# sparkfun-mlx90640-qwiic-breakout-55.net
KiCad netlist of a schematic drawn in EAGLE
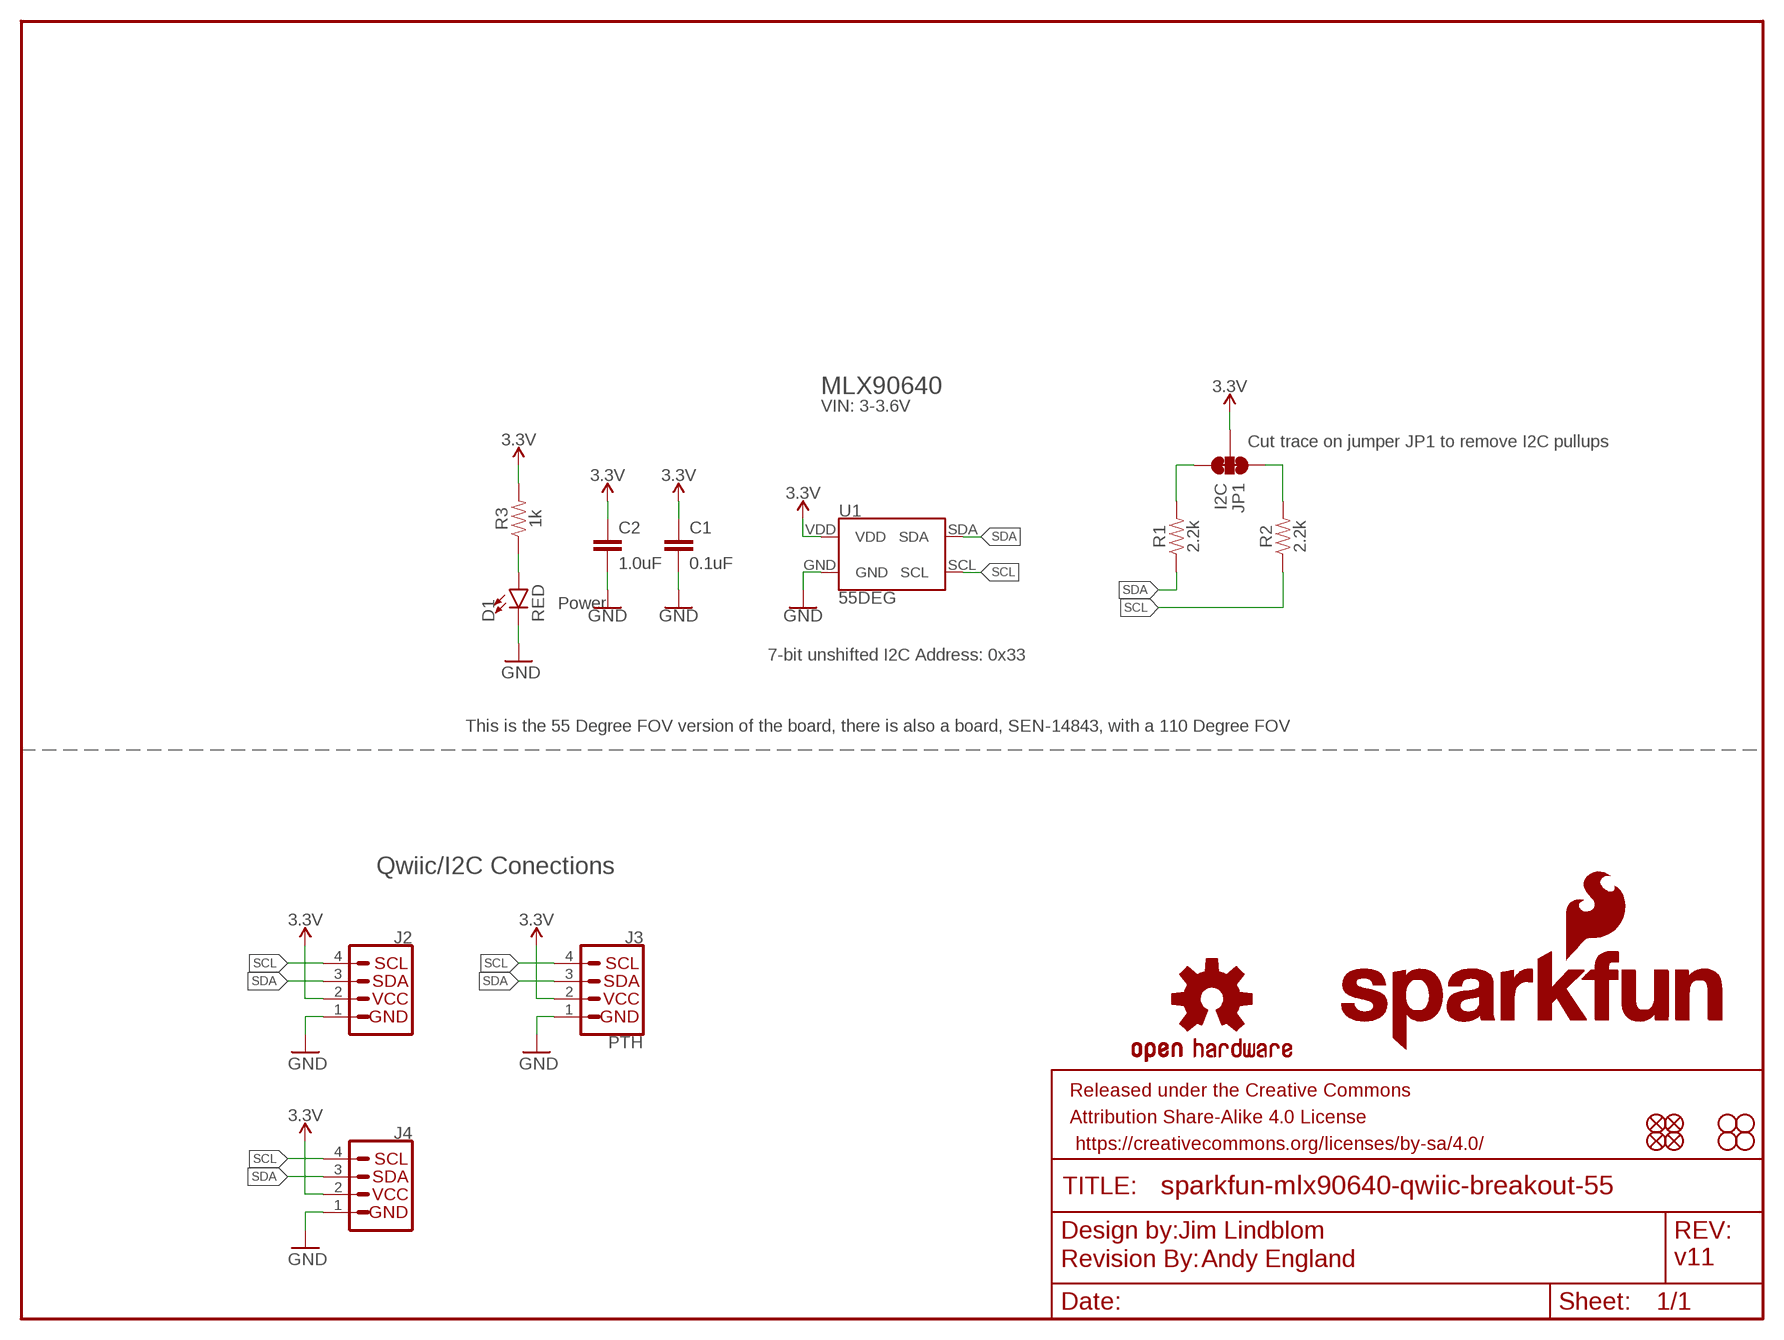
[diagram p0: schematic, sheet 1]

(export (version "E")
  (design (tool "Eeschema 10.0.6"))
  (components
    (comp (ref "C1")
      (value "0.1uF")
      (footprint "eagle-import:0603")
      (libsource (lib "eagle-import") (part "0.1UF-0603-25V-(+80/-20%)"))
    )
    (comp (ref "C2")
      (value "1.0uF")
      (footprint "eagle-import:0603")
      (libsource (lib "eagle-import") (part "1.0UF-0603-16V-10%"))
    )
    (comp (ref "D1")
      (value "RED")
      (footprint "eagle-import:LED-0603")
      (libsource (lib "eagle-import") (part "LED-RED0603"))
    )
    (comp (ref "FRAME1")
      (value "FRAME-LETTER")
      (footprint "eagle-import:CREATIVE_COMMONS")
      (libsource (lib "eagle-import") (part "FRAME-LETTER"))
    )
    (comp (ref "J2")
      (value "QWIIC_CONNECTORJS-1MM")
      (footprint "eagle-import:1X04_1MM_RA")
      (libsource (lib "eagle-import") (part "QWIIC_CONNECTORJS-1MM"))
    )
    (comp (ref "J3")
      (value "PTH")
      (footprint "eagle-import:1X04_NO_SILK")
      (libsource (lib "eagle-import") (part "I2C_STANDARD_NO_SILK"))
    )
    (comp (ref "J4")
      (value "QWIIC_CONNECTORJS-1MM")
      (footprint "eagle-import:1X04_1MM_RA")
      (libsource (lib "eagle-import") (part "QWIIC_CONNECTORJS-1MM"))
    )
    (comp (ref "JP1")
      (value "I2C")
      (footprint "eagle-import:SMT-JUMPER_3_2-NC_TRACE_NO-SILK")
      (libsource (lib "eagle-import") (part "JUMPER-SMT_3_2-NC_TRACE_NO-SILK"))
    )
    (comp (ref "JP2")
      (value "FIDUCIALUFIDUCIAL")
      (footprint "eagle-import:MICRO-FIDUCIAL")
      (libsource (lib "eagle-import") (part "FIDUCIALUFIDUCIAL"))
    )
    (comp (ref "JP3")
      (value "STAND-OFF")
      (footprint "eagle-import:STAND-OFF")
      (libsource (lib "eagle-import") (part "STAND-OFF"))
    )
    (comp (ref "JP4")
      (value "STAND-OFF")
      (footprint "eagle-import:STAND-OFF")
      (libsource (lib "eagle-import") (part "STAND-OFF"))
    )
    (comp (ref "JP5")
      (value "FIDUCIALUFIDUCIAL")
      (footprint "eagle-import:MICRO-FIDUCIAL")
      (libsource (lib "eagle-import") (part "FIDUCIALUFIDUCIAL"))
    )
    (comp (ref "JP6")
      (value "FIDUCIALUFIDUCIAL")
      (footprint "eagle-import:MICRO-FIDUCIAL")
      (libsource (lib "eagle-import") (part "FIDUCIALUFIDUCIAL"))
    )
    (comp (ref "JP7")
      (value "FIDUCIALUFIDUCIAL")
      (footprint "eagle-import:MICRO-FIDUCIAL")
      (libsource (lib "eagle-import") (part "FIDUCIALUFIDUCIAL"))
    )
    (comp (ref "JP8")
      (value "STAND-OFF")
      (footprint "eagle-import:STAND-OFF")
      (libsource (lib "eagle-import") (part "STAND-OFF"))
    )
    (comp (ref "JP9")
      (value "STAND-OFF")
      (footprint "eagle-import:STAND-OFF")
      (libsource (lib "eagle-import") (part "STAND-OFF"))
    )
    (comp (ref "LOGO1")
      (value "OSHW-LOGOMINI")
      (footprint "eagle-import:OSHW-LOGO-MINI")
      (libsource (lib "eagle-import") (part "OSHW-LOGOMINI"))
    )
    (comp (ref "LOGO2")
      (value "SFE_LOGO_NAME_FLAME.1_INCH")
      (footprint "eagle-import:SFE_LOGO_NAME_FLAME_.1")
      (libsource (lib "eagle-import") (part "SFE_LOGO_NAME_FLAME.1_INCH"))
    )
    (comp (ref "LOGO3")
      (value "SFE_LOGO_NAME.1_INCH")
      (footprint "eagle-import:SFE_LOGO_NAME_.1")
      (libsource (lib "eagle-import") (part "SFE_LOGO_NAME.1_INCH"))
    )
    (comp (ref "LOGO4")
      (value "REVISION")
      (footprint "eagle-import:REVISION")
      (libsource (lib "eagle-import") (part "REVISION"))
    )
    (comp (ref "R1")
      (value "2.2k")
      (footprint "eagle-import:0603")
      (libsource (lib "eagle-import") (part "2.2KOHM-0603-1/10W-1%"))
    )
    (comp (ref "R2")
      (value "2.2k")
      (footprint "eagle-import:0603")
      (libsource (lib "eagle-import") (part "2.2KOHM-0603-1/10W-1%"))
    )
    (comp (ref "R3")
      (value "1k")
      (footprint "eagle-import:0603")
      (libsource (lib "eagle-import") (part "1KOHM-0603-1/10W-1%"))
    )
    (comp (ref "U1")
      (value "55DEG")
      (footprint "eagle-import:MLX90540_MLX90640")
      (libsource (lib "eagle-import") (part "MLX90540_MLX90640"))
    )
  )
  (nets
    (net (code "1") (name "3.3V") (class "Default")
      (node (ref "C1") (pin "1") (pinfunction "1_1") (pintype "passive"))
      (node (ref "C2") (pin "1") (pinfunction "1_1") (pintype "passive"))
      (node (ref "J2") (pin "2") (pinfunction "2_2") (pintype "power_in"))
      (node (ref "J3") (pin "2") (pinfunction "VCC_2") (pintype "power_in"))
      (node (ref "J4") (pin "2") (pinfunction "2_2") (pintype "power_in"))
      (node (ref "JP1") (pin "2") (pinfunction "2_2") (pintype "passive"))
      (node (ref "R3") (pin "2") (pinfunction "2_2") (pintype "passive"))
      (node (ref "U1") (pin "VDD") (pinfunction "VDD_VDD") (pintype "bidirectional"))
    )
    (net (code "2") (name "GND") (class "Default")
      (node (ref "C1") (pin "2") (pinfunction "2_2") (pintype "passive"))
      (node (ref "C2") (pin "2") (pinfunction "2_2") (pintype "passive"))
      (node (ref "D1") (pin "C") (pinfunction "C_C") (pintype "passive"))
      (node (ref "J2") (pin "1") (pinfunction "1_1") (pintype "power_in"))
      (node (ref "J3") (pin "1") (pinfunction "GND_1") (pintype "power_in"))
      (node (ref "J4") (pin "1") (pinfunction "1_1") (pintype "power_in"))
      (node (ref "U1") (pin "GND") (pinfunction "GND_GND") (pintype "bidirectional"))
    )
    (net (code "3") (name "Net-(D1-PadA)") (class "Default")
      (node (ref "D1") (pin "A") (pinfunction "A_A") (pintype "passive"))
      (node (ref "R3") (pin "1") (pinfunction "1_1") (pintype "passive"))
    )
    (net (code "4") (name "Net-(JP1-Pad1)") (class "Default")
      (node (ref "JP1") (pin "1") (pinfunction "1_1") (pintype "passive"))
      (node (ref "R2") (pin "2") (pinfunction "2_2") (pintype "passive"))
    )
    (net (code "5") (name "Net-(JP1-Pad3)") (class "Default")
      (node (ref "JP1") (pin "3") (pinfunction "3_3") (pintype "passive"))
      (node (ref "R1") (pin "2") (pinfunction "2_2") (pintype "passive"))
    )
    (net (code "6") (name "SCL") (class "Default")
      (node (ref "J2") (pin "4") (pinfunction "4_4") (pintype "passive"))
      (node (ref "J3") (pin "4") (pinfunction "SCL_4") (pintype "passive"))
      (node (ref "J4") (pin "4") (pinfunction "4_4") (pintype "passive"))
      (node (ref "R2") (pin "1") (pinfunction "1_1") (pintype "passive"))
      (node (ref "U1") (pin "SCL") (pinfunction "SCL_SCL") (pintype "bidirectional"))
    )
    (net (code "7") (name "SDA") (class "Default")
      (node (ref "J2") (pin "3") (pinfunction "3_3") (pintype "passive"))
      (node (ref "J3") (pin "3") (pinfunction "SDA_3") (pintype "passive"))
      (node (ref "J4") (pin "3") (pinfunction "3_3") (pintype "passive"))
      (node (ref "R1") (pin "1") (pinfunction "1_1") (pintype "passive"))
      (node (ref "U1") (pin "SDA") (pinfunction "SDA_SDA") (pintype "bidirectional"))
    )
  )
)
